# Battery_Shield.net
KiCad netlist of a schematic drawn in EAGLE
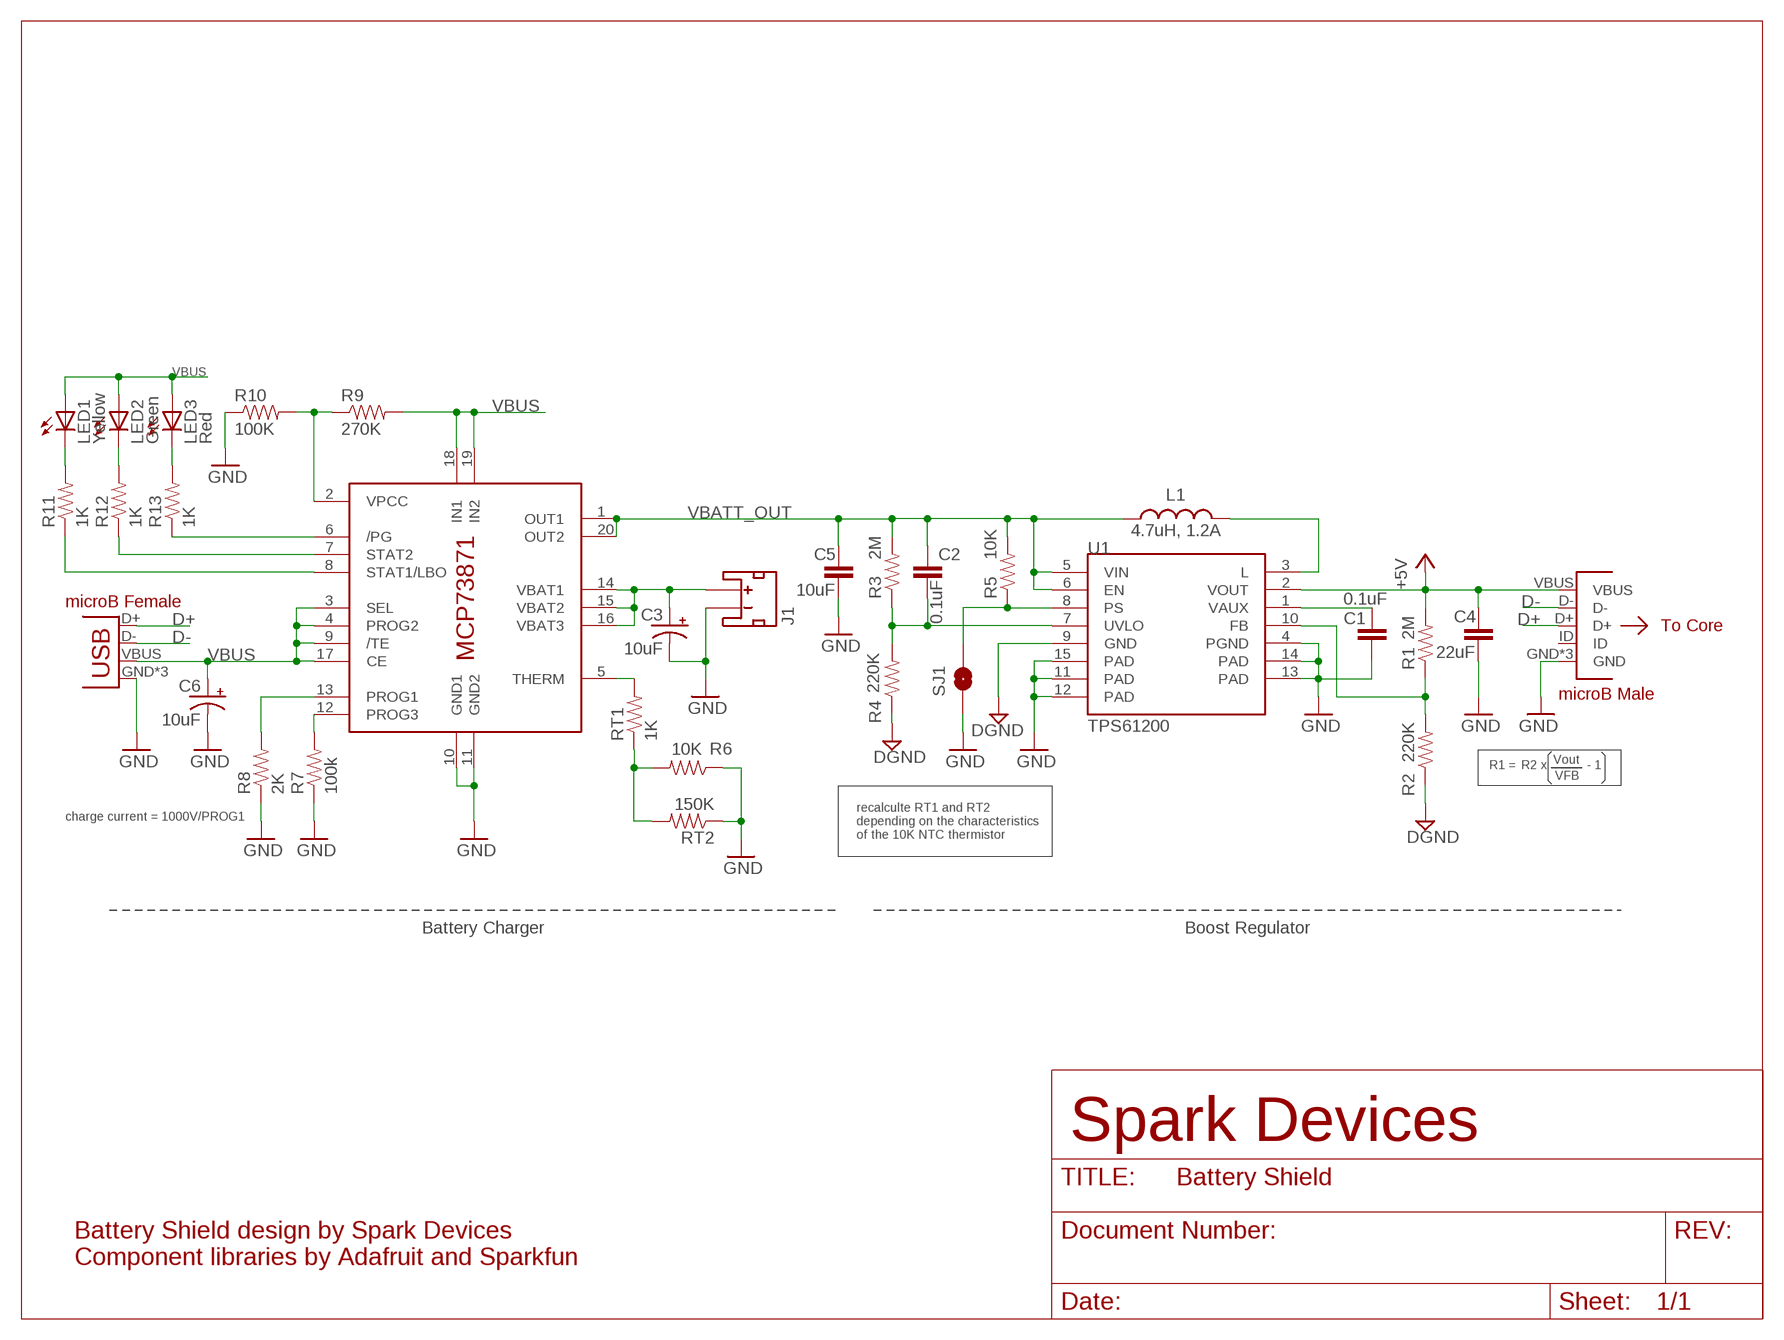
[diagram p0: schematic, sheet 1]

(export (version "E")
  (design (tool "Eeschema 10.0.6"))
  (components
    (comp (ref "C1")
      (value "0.1uF")
      (footprint "eagle-import:0402-CAP")
      (libsource (lib "eagle-import") (part "SparkFun-Passives_CAP0402-CAP"))
    )
    (comp (ref "C2")
      (value "0.1uF")
      (footprint "eagle-import:0402-CAP")
      (libsource (lib "eagle-import") (part "SparkFun-Passives_CAP0402-CAP"))
    )
    (comp (ref "C3")
      (value "10uF")
      (footprint "eagle-import:EIA3216")
      (libsource (lib "eagle-import") (part "10UF-16V-10%(TANT)"))
    )
    (comp (ref "C4")
      (value "22uF")
      (footprint "eagle-import:0805")
      (libsource (lib "eagle-import") (part "SparkFun-Passives_CAP0805"))
    )
    (comp (ref "C5")
      (value "10uF")
      (footprint "eagle-import:1206")
      (libsource (lib "eagle-import") (part "CAP1206"))
    )
    (comp (ref "C6")
      (value "10uF")
      (footprint "eagle-import:EIA3216")
      (fields (field (name "PROD_ID") "CAP-00811"))
      (libsource (lib "eagle-import") (part "10UF-16V-10%(TANT)"))
    )
    (comp (ref "IC1")
      (value "MCP73871")
      (footprint "eagle-import:QFN20")
      (libsource (lib "eagle-import") (part "MCP73871"))
    )
    (comp (ref "J1")
      (value "JST_2MM_MALE")
      (footprint "eagle-import:JST-2-SMD")
      (libsource (lib "eagle-import") (part "JST_2MM_MALE"))
    )
    (comp (ref "JP1")
      (value "USBUSB-MICROB-SLOT-HOLE")
      (footprint "eagle-import:USB-MICROB-SLOT-HOLE")
      (libsource (lib "eagle-import") (part "USBUSB-MICROB-SLOT-HOLE"))
    )
    (comp (ref "L1")
      (value "4.7uH, 1.2A")
      (footprint "eagle-import:CDRH2D09")
      (libsource (lib "eagle-import") (part "INDUCTOR."))
    )
    (comp (ref "LED1")
      (value "Yellow")
      (footprint "eagle-import:LED-0603")
      (libsource (lib "eagle-import") (part "LED0603"))
    )
    (comp (ref "LED2")
      (value "Green")
      (footprint "eagle-import:LED-0603")
      (libsource (lib "eagle-import") (part "LED0603"))
    )
    (comp (ref "LED3")
      (value "Red")
      (footprint "eagle-import:LED-0603")
      (libsource (lib "eagle-import") (part "LED0603"))
    )
    (comp (ref "R1")
      (value "2M")
      (footprint "eagle-import:0402-RES")
      (libsource (lib "eagle-import") (part "RESISTOR0402-RES"))
    )
    (comp (ref "R2")
      (value "220K")
      (footprint "eagle-import:0402-RES")
      (libsource (lib "eagle-import") (part "RESISTOR0402-RES"))
    )
    (comp (ref "R3")
      (value "2M")
      (footprint "eagle-import:0402-RES")
      (libsource (lib "eagle-import") (part "RESISTOR0402-RES"))
    )
    (comp (ref "R4")
      (value "220K")
      (footprint "eagle-import:0402-RES")
      (libsource (lib "eagle-import") (part "RESISTOR0402-RES"))
    )
    (comp (ref "R5")
      (value "10K")
      (footprint "eagle-import:0402-RES")
      (libsource (lib "eagle-import") (part "RESISTOR0402-RES"))
    )
    (comp (ref "R6")
      (value "10K")
      (footprint "eagle-import:0402-RES")
      (libsource (lib "eagle-import") (part "RESISTOR0402-RES"))
    )
    (comp (ref "R7")
      (value "100k")
      (footprint "eagle-import:0402-RES")
      (libsource (lib "eagle-import") (part "RESISTOR0402-RES"))
    )
    (comp (ref "R8")
      (value "2K")
      (footprint "eagle-import:0402-RES")
      (libsource (lib "eagle-import") (part "RESISTOR0402-RES"))
    )
    (comp (ref "R9")
      (value "270K")
      (footprint "eagle-import:0402-RES")
      (libsource (lib "eagle-import") (part "RESISTOR0402-RES"))
    )
    (comp (ref "R10")
      (value "100K")
      (footprint "eagle-import:0402-RES")
      (libsource (lib "eagle-import") (part "RESISTOR0402-RES"))
    )
    (comp (ref "R11")
      (value "1K")
      (footprint "eagle-import:0402-RES")
      (libsource (lib "eagle-import") (part "RESISTOR0402-RES"))
    )
    (comp (ref "R12")
      (value "1K")
      (footprint "eagle-import:0402-RES")
      (libsource (lib "eagle-import") (part "RESISTOR0402-RES"))
    )
    (comp (ref "R13")
      (value "1K")
      (footprint "eagle-import:0402-RES")
      (libsource (lib "eagle-import") (part "RESISTOR0402-RES"))
    )
    (comp (ref "RT1")
      (value "1K")
      (footprint "eagle-import:0402-RES")
      (libsource (lib "eagle-import") (part "RESISTOR0402-RES"))
    )
    (comp (ref "RT2")
      (value "150K")
      (footprint "eagle-import:0402-RES")
      (libsource (lib "eagle-import") (part "RESISTOR0402-RES"))
    )
    (comp (ref "SJ1")
      (value "SOLDERJUMPERNO")
      (footprint "eagle-import:SJ_2S-NO")
      (libsource (lib "eagle-import") (part "SOLDERJUMPERNO"))
    )
    (comp (ref "U$1")
      (value "USB_MALE")
      (footprint "eagle-import:USB-MICROB-MALE-SANDWICH")
      (libsource (lib "eagle-import") (part "USB_MALE"))
    )
    (comp (ref "U1")
      (value "TPS61200")
      (footprint "eagle-import:QFN-10_PAD")
      (libsource (lib "eagle-import") (part "TPS61200"))
    )
  )
  (nets
    (net (code "1") (name "+5V") (class "Default")
      (node (ref "C4") (pin "1") (pinfunction "1_1") (pintype "passive"))
      (node (ref "R1") (pin "2") (pinfunction "2_2") (pintype "passive"))
      (node (ref "U$1") (pin "VBUS") (pinfunction "VBUS_VBUS") (pintype "power_in"))
      (node (ref "U1") (pin "2") (pinfunction "VOUT_2") (pintype "passive"))
    )
    (net (code "2") (name "/D+") (class "Default")
      (node (ref "JP1") (pin "D+") (pinfunction "D+_D+") (pintype "bidirectional"))
      (node (ref "U$1") (pin "D+") (pinfunction "D+_D+") (pintype "bidirectional"))
    )
    (net (code "3") (name "/D-") (class "Default")
      (node (ref "JP1") (pin "D-") (pinfunction "D-_D-") (pintype "bidirectional"))
      (node (ref "U$1") (pin "D-") (pinfunction "D-_D-") (pintype "bidirectional"))
    )
    (net (code "4") (name "/VBATT_OUT") (class "Default")
      (node (ref "C2") (pin "1") (pinfunction "1_1") (pintype "passive"))
      (node (ref "C5") (pin "1") (pinfunction "1_1") (pintype "passive"))
      (node (ref "IC1") (pin "1") (pinfunction "OUT1_1") (pintype "output"))
      (node (ref "IC1") (pin "20") (pinfunction "OUT2_20") (pintype "output"))
      (node (ref "L1") (pin "P$1") (pinfunction "1_P$1") (pintype "passive"))
      (node (ref "R3") (pin "2") (pinfunction "2_2") (pintype "passive"))
      (node (ref "R5") (pin "2") (pinfunction "2_2") (pintype "passive"))
      (node (ref "U1") (pin "5") (pinfunction "VIN_5") (pintype "power_in"))
      (node (ref "U1") (pin "6") (pinfunction "EN_6") (pintype "input"))
    )
    (net (code "5") (name "/VBUS") (class "Default")
      (node (ref "C6") (pin "A") (pinfunction "+_A") (pintype "passive"))
      (node (ref "IC1") (pin "17") (pinfunction "CE_17") (pintype "input"))
      (node (ref "IC1") (pin "18") (pinfunction "IN1_18") (pintype "input"))
      (node (ref "IC1") (pin "19") (pinfunction "IN2_19") (pintype "input"))
      (node (ref "IC1") (pin "3") (pinfunction "SEL_3") (pintype "input"))
      (node (ref "IC1") (pin "4") (pinfunction "PROG2_4") (pintype "input"))
      (node (ref "IC1") (pin "9") (pinfunction "/TE_9") (pintype "input"))
      (node (ref "JP1") (pin "VBUS") (pinfunction "VBUS_VBUS") (pintype "bidirectional"))
      (node (ref "LED1") (pin "A") (pinfunction "A_A") (pintype "passive"))
      (node (ref "LED2") (pin "A") (pinfunction "A_A") (pintype "passive"))
      (node (ref "LED3") (pin "A") (pinfunction "A_A") (pintype "passive"))
      (node (ref "R9") (pin "2") (pinfunction "2_2") (pintype "passive"))
    )
    (net (code "6") (name "DGND") (class "Default")
      (node (ref "R2") (pin "1") (pinfunction "1_1") (pintype "passive"))
      (node (ref "R4") (pin "1") (pinfunction "1_1") (pintype "passive"))
      (node (ref "U1") (pin "9") (pinfunction "GND_9") (pintype "power_in"))
    )
    (net (code "7") (name "GND") (class "Default")
      (node (ref "C1") (pin "2") (pinfunction "2_2") (pintype "passive"))
      (node (ref "C3") (pin "C") (pinfunction "-_C") (pintype "passive"))
      (node (ref "C4") (pin "2") (pinfunction "2_2") (pintype "passive"))
      (node (ref "C5") (pin "2") (pinfunction "2_2") (pintype "passive"))
      (node (ref "C6") (pin "C") (pinfunction "-_C") (pintype "passive"))
      (node (ref "IC1") (pin "10") (pinfunction "GND1_10") (pintype "power_in"))
      (node (ref "IC1") (pin "11") (pinfunction "GND2_11") (pintype "power_in"))
      (node (ref "J1") (pin "1") (pinfunction "-_1") (pintype "bidirectional"))
      (node (ref "JP1") (pin "GND") (pinfunction "GND_GND") (pintype "bidirectional"))
      (node (ref "JP1") (pin "MT1") (pinfunction "GND_MT1") (pintype "bidirectional"))
      (node (ref "JP1") (pin "MT2") (pinfunction "GND_MT2") (pintype "bidirectional"))
      (node (ref "R10") (pin "1") (pinfunction "1_1") (pintype "passive"))
      (node (ref "R6") (pin "1") (pinfunction "1_1") (pintype "passive"))
      (node (ref "R7") (pin "1") (pinfunction "1_1") (pintype "passive"))
      (node (ref "R8") (pin "1") (pinfunction "1_1") (pintype "passive"))
      (node (ref "RT2") (pin "1") (pinfunction "1_1") (pintype "passive"))
      (node (ref "SJ1") (pin "1") (pinfunction "1_1") (pintype "passive"))
      (node (ref "U$1") (pin "GND") (pinfunction "GND_GND") (pintype "power_in"))
      (node (ref "U$1") (pin "GNDPAD1") (pinfunction "GND_GNDPAD1") (pintype "power_in"))
      (node (ref "U$1") (pin "GNDPAD2") (pinfunction "GND_GNDPAD2") (pintype "power_in"))
      (node (ref "U1") (pin "11") (pinfunction "PAD_11") (pintype "power_in"))
      (node (ref "U1") (pin "12") (pinfunction "PAD_12") (pintype "power_in"))
      (node (ref "U1") (pin "13") (pinfunction "PAD_13") (pintype "power_in"))
      (node (ref "U1") (pin "14") (pinfunction "PAD_14") (pintype "power_in"))
      (node (ref "U1") (pin "15") (pinfunction "PAD_15") (pintype "power_in"))
      (node (ref "U1") (pin "4") (pinfunction "PGND_4") (pintype "power_in"))
    )
    (net (code "8") (name "Net-(C3-+)") (class "Default")
      (node (ref "C3") (pin "A") (pinfunction "+_A") (pintype "passive"))
      (node (ref "IC1") (pin "14") (pinfunction "VBAT1_14") (pintype "output"))
      (node (ref "IC1") (pin "15") (pinfunction "VBAT2_15") (pintype "output"))
      (node (ref "IC1") (pin "16") (pinfunction "VBAT3_16") (pintype "output"))
      (node (ref "J1") (pin "2") (pinfunction "+_2") (pintype "bidirectional"))
    )
    (net (code "9") (name "Net-(IC1-PROG1)") (class "Default")
      (node (ref "IC1") (pin "13") (pinfunction "PROG1_13") (pintype "input"))
      (node (ref "R8") (pin "2") (pinfunction "2_2") (pintype "passive"))
    )
    (net (code "10") (name "Net-(IC1-PROG3)") (class "Default")
      (node (ref "IC1") (pin "12") (pinfunction "PROG3_12") (pintype "input"))
      (node (ref "R7") (pin "2") (pinfunction "2_2") (pintype "passive"))
    )
    (net (code "11") (name "Net-(IC1-STAT1{slash}LBO)") (class "Default")
      (node (ref "IC1") (pin "8") (pinfunction "STAT1/LBO_8") (pintype "output"))
      (node (ref "R11") (pin "1") (pinfunction "1_1") (pintype "passive"))
    )
    (net (code "12") (name "Net-(IC1-STAT2)") (class "Default")
      (node (ref "IC1") (pin "7") (pinfunction "STAT2_7") (pintype "output"))
      (node (ref "R12") (pin "1") (pinfunction "1_1") (pintype "passive"))
    )
    (net (code "13") (name "Net-(IC1-THERM)") (class "Default")
      (node (ref "IC1") (pin "5") (pinfunction "THERM_5") (pintype "input"))
      (node (ref "RT1") (pin "2") (pinfunction "2_2") (pintype "passive"))
    )
    (net (code "14") (name "Net-(IC1-VPCC)") (class "Default")
      (node (ref "IC1") (pin "2") (pinfunction "VPCC_2") (pintype "input"))
      (node (ref "R10") (pin "2") (pinfunction "2_2") (pintype "passive"))
      (node (ref "R9") (pin "1") (pinfunction "1_1") (pintype "passive"))
    )
    (net (code "15") (name "Net-(IC1-{slash}PG)") (class "Default")
      (node (ref "IC1") (pin "6") (pinfunction "/PG_6") (pintype "output"))
      (node (ref "R13") (pin "1") (pinfunction "1_1") (pintype "passive"))
    )
    (net (code "16") (name "Net-(L1-2)") (class "Default")
      (node (ref "L1") (pin "P$2") (pinfunction "2_P$2") (pintype "passive"))
      (node (ref "U1") (pin "3") (pinfunction "L_3") (pintype "passive"))
    )
    (net (code "17") (name "Net-(LED1-PadC)") (class "Default")
      (node (ref "LED1") (pin "C") (pinfunction "C_C") (pintype "passive"))
      (node (ref "R11") (pin "2") (pinfunction "2_2") (pintype "passive"))
    )
    (net (code "18") (name "Net-(LED2-PadC)") (class "Default")
      (node (ref "LED2") (pin "C") (pinfunction "C_C") (pintype "passive"))
      (node (ref "R12") (pin "2") (pinfunction "2_2") (pintype "passive"))
    )
    (net (code "19") (name "Net-(LED3-PadC)") (class "Default")
      (node (ref "LED3") (pin "C") (pinfunction "C_C") (pintype "passive"))
      (node (ref "R13") (pin "2") (pinfunction "2_2") (pintype "passive"))
    )
    (net (code "20") (name "Net-(R6-Pad2)") (class "Default")
      (node (ref "R6") (pin "2") (pinfunction "2_2") (pintype "passive"))
      (node (ref "RT1") (pin "1") (pinfunction "1_1") (pintype "passive"))
      (node (ref "RT2") (pin "2") (pinfunction "2_2") (pintype "passive"))
    )
    (net (code "21") (name "Net-(U1-FB)") (class "Default")
      (node (ref "R1") (pin "1") (pinfunction "1_1") (pintype "passive"))
      (node (ref "R2") (pin "2") (pinfunction "2_2") (pintype "passive"))
      (node (ref "U1") (pin "10") (pinfunction "FB_10") (pintype "passive"))
    )
    (net (code "22") (name "Net-(U1-PS)") (class "Default")
      (node (ref "R5") (pin "1") (pinfunction "1_1") (pintype "passive"))
      (node (ref "SJ1") (pin "2") (pinfunction "2_2") (pintype "passive"))
      (node (ref "U1") (pin "8") (pinfunction "PS_8") (pintype "input"))
    )
    (net (code "23") (name "Net-(U1-UVLO)") (class "Default")
      (node (ref "C2") (pin "2") (pinfunction "2_2") (pintype "passive"))
      (node (ref "R3") (pin "1") (pinfunction "1_1") (pintype "passive"))
      (node (ref "R4") (pin "2") (pinfunction "2_2") (pintype "passive"))
      (node (ref "U1") (pin "7") (pinfunction "UVLO_7") (pintype "passive"))
    )
    (net (code "24") (name "Net-(U1-VAUX)") (class "Default")
      (node (ref "C1") (pin "1") (pinfunction "1_1") (pintype "passive"))
      (node (ref "U1") (pin "1") (pinfunction "VAUX_1") (pintype "passive"))
    )
    (net (code "25") (name "unconnected-(J1-PAD1-PadNC1)") (class "Default")
      (node (ref "J1") (pin "NC1") (pinfunction "PAD1_NC1") (pintype "bidirectional"))
    )
    (net (code "26") (name "unconnected-(J1-PAD2-PadNC2)") (class "Default")
      (node (ref "J1") (pin "NC2") (pinfunction "PAD2_NC2") (pintype "bidirectional"))
    )
    (net (code "27") (name "unconnected-(U$1-PadID)") (class "Default")
      (node (ref "U$1") (pin "ID") (pinfunction "ID_ID") (pintype "bidirectional"))
    )
  )
)
